# LampV1.net
KiCad netlist of a schematic drawn in EAGLE
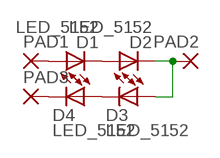
[diagram p0: schematic, sheet 1]

(export (version "E")
  (design (tool "Eeschema 10.0.6"))
  (components
    (comp (ref "D1")
      (value "LED_5152")
      (footprint "eagle-import:LED-5152")
      (libsource (lib "eagle-import") (part "LED_5152"))
    )
    (comp (ref "D2")
      (value "LED_5152")
      (footprint "eagle-import:LED-5152")
      (libsource (lib "eagle-import") (part "LED_5152"))
    )
    (comp (ref "D3")
      (value "LED_5152")
      (footprint "eagle-import:LED-5152")
      (libsource (lib "eagle-import") (part "LED_5152"))
    )
    (comp (ref "D4")
      (value "LED_5152")
      (footprint "eagle-import:LED-5152")
      (libsource (lib "eagle-import") (part "LED_5152"))
    )
    (comp (ref "PAD1")
      (value "2,54/1,1")
      (footprint "eagle-import:2,54_1,1")
      (libsource (lib "eagle-import") (part "2,54/1,1"))
    )
    (comp (ref "PAD2")
      (value "2,54/1,1")
      (footprint "eagle-import:2,54_1,1")
      (libsource (lib "eagle-import") (part "2,54/1,1"))
    )
    (comp (ref "PAD3")
      (value "2,54/1,1")
      (footprint "eagle-import:2,54_1,1")
      (libsource (lib "eagle-import") (part "2,54/1,1"))
    )
  )
  (nets
    (net (code "1") (name "Net-(D1-PadC)") (class "Default")
      (node (ref "D1") (pin "C") (pinfunction "C_C") (pintype "passive"))
      (node (ref "D2") (pin "A") (pinfunction "A_A") (pintype "passive"))
    )
    (net (code "2") (name "Net-(D3-PadC)") (class "Default")
      (node (ref "D3") (pin "C") (pinfunction "C_C") (pintype "passive"))
      (node (ref "D4") (pin "A") (pinfunction "A_A") (pintype "passive"))
    )
    (net (code "3") (name "Net-(PAD1-P)") (class "Default")
      (node (ref "D1") (pin "A") (pinfunction "A_A") (pintype "passive"))
      (node (ref "PAD1") (pin "1") (pinfunction "P_1") (pintype "passive"))
    )
    (net (code "4") (name "Net-(PAD2-P)") (class "Default")
      (node (ref "D2") (pin "C") (pinfunction "C_C") (pintype "passive"))
      (node (ref "D3") (pin "A") (pinfunction "A_A") (pintype "passive"))
      (node (ref "PAD2") (pin "1") (pinfunction "P_1") (pintype "passive"))
    )
    (net (code "5") (name "Net-(PAD3-P)") (class "Default")
      (node (ref "D4") (pin "C") (pinfunction "C_C") (pintype "passive"))
      (node (ref "PAD3") (pin "1") (pinfunction "P_1") (pintype "passive"))
    )
  )
)
